# OSSI-1_COMMS_2.net
KiCad netlist of a schematic drawn in Altium Designer
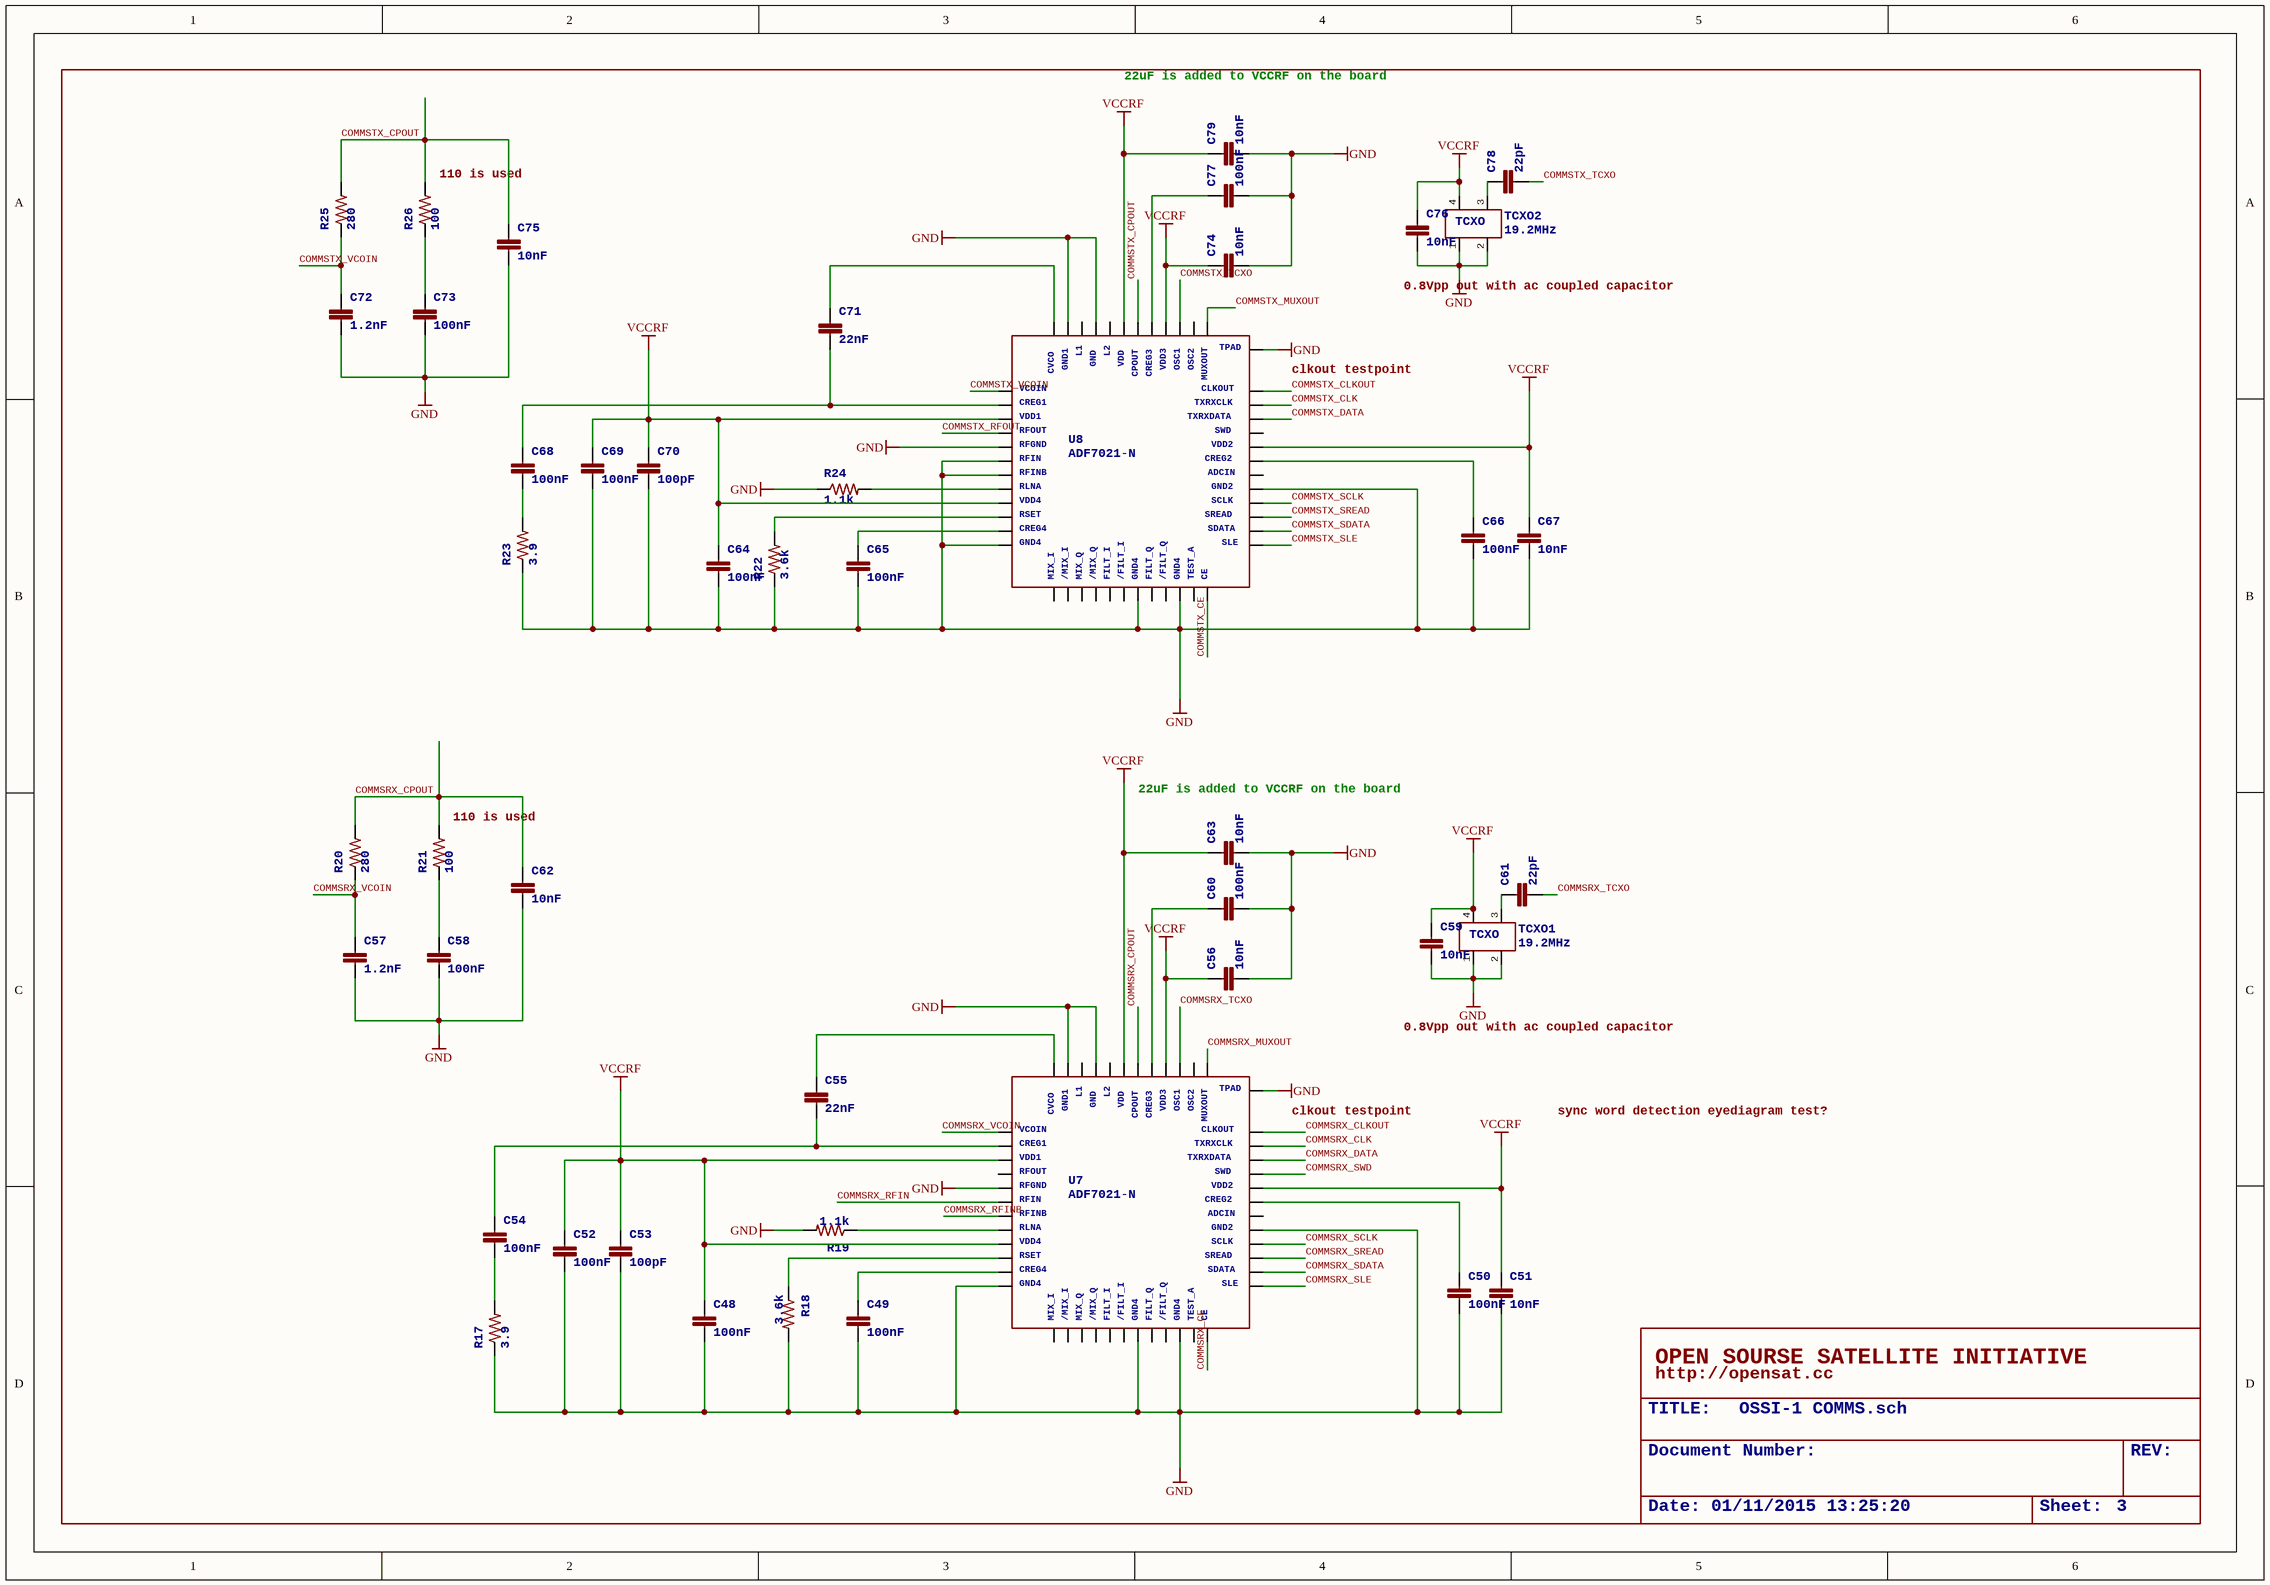
[diagram p0: OSSI-1 COMMS_2.SchDoc]

(export (version "E")
  (design (tool "Eeschema 10.0.6"))
  (components
    (comp (ref "C48")
      (value "100nF")
      (footprint "C0603(1608)")
      (fields (field (name ">NAME") "C48") (field (name ">VALUE") "100nF"))
      (libsource (lib "OSSI") (part "C0603(1608)"))
    )
    (comp (ref "C49")
      (value "100nF")
      (footprint "C0603(1608)")
      (fields (field (name ">NAME") "C49") (field (name ">VALUE") "100nF"))
      (libsource (lib "OSSI") (part "C0603(1608)"))
    )
    (comp (ref "C50")
      (value "100nF")
      (footprint "C0603(1608)")
      (fields (field (name ">NAME") "C50") (field (name ">VALUE") "100nF"))
      (libsource (lib "OSSI") (part "C0603(1608)"))
    )
    (comp (ref "C51")
      (value "10nF")
      (footprint "C0603(1608)")
      (fields (field (name ">NAME") "C51") (field (name ">VALUE") "10nF"))
      (libsource (lib "OSSI") (part "C0603(1608)"))
    )
    (comp (ref "C52")
      (value "100nF")
      (footprint "C0603(1608)")
      (fields (field (name ">NAME") "C52") (field (name ">VALUE") "100nF"))
      (libsource (lib "OSSI") (part "C0603(1608)"))
    )
    (comp (ref "C53")
      (value "100pF")
      (footprint "C0603(1608)")
      (fields (field (name ">NAME") "C53") (field (name ">VALUE") "100pF"))
      (libsource (lib "OSSI") (part "C0603(1608)"))
    )
    (comp (ref "C54")
      (value "100nF")
      (footprint "C0603(1608)")
      (fields (field (name ">NAME") "C54") (field (name ">VALUE") "100nF"))
      (libsource (lib "OSSI") (part "C0603(1608)"))
    )
    (comp (ref "C55")
      (value "22nF")
      (footprint "C0603(1608)")
      (fields (field (name ">NAME") "C55") (field (name ">VALUE") "22nF"))
      (libsource (lib "OSSI") (part "C0603(1608)"))
    )
    (comp (ref "C56")
      (value "10nF")
      (footprint "C0603(1608)")
      (fields (field (name ">NAME") "C56") (field (name ">VALUE") "10nF"))
      (libsource (lib "") (part "C0603(1608)_1"))
    )
    (comp (ref "C57")
      (value "1.2nF")
      (footprint "C0603(1608)")
      (fields (field (name ">NAME") "C57") (field (name ">VALUE") "1.2nF"))
      (libsource (lib "OSSI") (part "C0603(1608)"))
    )
    (comp (ref "C58")
      (value "100nF")
      (footprint "C0603(1608)")
      (fields (field (name ">NAME") "C58") (field (name ">VALUE") "100nF"))
      (libsource (lib "OSSI") (part "C0603(1608)"))
    )
    (comp (ref "C59")
      (value "10nF")
      (footprint "C0603(1608)")
      (fields (field (name ">NAME") "C59") (field (name ">VALUE") "10nF"))
      (libsource (lib "OSSI") (part "C0603(1608)"))
    )
    (comp (ref "C60")
      (value "100nF")
      (footprint "C0603(1608)")
      (fields (field (name ">NAME") "C60") (field (name ">VALUE") "100nF"))
      (libsource (lib "") (part "C0603(1608)_1"))
    )
    (comp (ref "C61")
      (value "22pF")
      (footprint "C0603(1608)")
      (fields (field (name ">NAME") "C61") (field (name ">VALUE") "22pF"))
      (libsource (lib "") (part "C0603(1608)_1"))
    )
    (comp (ref "C62")
      (value "10nF")
      (footprint "C0603(1608)")
      (fields (field (name ">NAME") "C62") (field (name ">VALUE") "10nF"))
      (libsource (lib "OSSI") (part "C0603(1608)"))
    )
    (comp (ref "C63")
      (value "10nF")
      (footprint "C0603(1608)")
      (fields (field (name ">NAME") "C63") (field (name ">VALUE") "10nF"))
      (libsource (lib "") (part "C0603(1608)_1"))
    )
    (comp (ref "C64")
      (value "100nF")
      (footprint "C0603(1608)")
      (fields (field (name ">NAME") "C64") (field (name ">VALUE") "100nF"))
      (libsource (lib "OSSI") (part "C0603(1608)"))
    )
    (comp (ref "C65")
      (value "100nF")
      (footprint "C0603(1608)")
      (fields (field (name ">NAME") "C65") (field (name ">VALUE") "100nF"))
      (libsource (lib "OSSI") (part "C0603(1608)"))
    )
    (comp (ref "C66")
      (value "100nF")
      (footprint "C0603(1608)")
      (fields (field (name ">NAME") "C66") (field (name ">VALUE") "100nF"))
      (libsource (lib "OSSI") (part "C0603(1608)"))
    )
    (comp (ref "C67")
      (value "10nF")
      (footprint "C0603(1608)")
      (fields (field (name ">NAME") "C67") (field (name ">VALUE") "10nF"))
      (libsource (lib "OSSI") (part "C0603(1608)"))
    )
    (comp (ref "C68")
      (value "100nF")
      (footprint "C0603(1608)")
      (fields (field (name ">NAME") "C68") (field (name ">VALUE") "100nF"))
      (libsource (lib "OSSI") (part "C0603(1608)"))
    )
    (comp (ref "C69")
      (value "100nF")
      (footprint "C0603(1608)")
      (fields (field (name ">NAME") "C69") (field (name ">VALUE") "100nF"))
      (libsource (lib "OSSI") (part "C0603(1608)"))
    )
    (comp (ref "C70")
      (value "100pF")
      (footprint "C0603(1608)")
      (fields (field (name ">NAME") "C70") (field (name ">VALUE") "100pF"))
      (libsource (lib "OSSI") (part "C0603(1608)"))
    )
    (comp (ref "C71")
      (value "22nF")
      (footprint "C0603(1608)")
      (fields (field (name ">NAME") "C71") (field (name ">VALUE") "22nF"))
      (libsource (lib "OSSI") (part "C0603(1608)"))
    )
    (comp (ref "C72")
      (value "1.2nF")
      (footprint "C0603(1608)")
      (fields (field (name ">NAME") "C72") (field (name ">VALUE") "1.2nF"))
      (libsource (lib "OSSI") (part "C0603(1608)"))
    )
    (comp (ref "C73")
      (value "100nF")
      (footprint "C0603(1608)")
      (fields (field (name ">NAME") "C73") (field (name ">VALUE") "100nF"))
      (libsource (lib "OSSI") (part "C0603(1608)"))
    )
    (comp (ref "C74")
      (value "10nF")
      (footprint "C0603(1608)")
      (fields (field (name ">NAME") "C74") (field (name ">VALUE") "10nF"))
      (libsource (lib "") (part "C0603(1608)_1"))
    )
    (comp (ref "C75")
      (value "10nF")
      (footprint "C0603(1608)")
      (fields (field (name ">NAME") "C75") (field (name ">VALUE") "10nF"))
      (libsource (lib "OSSI") (part "C0603(1608)"))
    )
    (comp (ref "C76")
      (value "10nF")
      (footprint "C0603(1608)")
      (fields (field (name ">NAME") "C76") (field (name ">VALUE") "10nF"))
      (libsource (lib "OSSI") (part "C0603(1608)"))
    )
    (comp (ref "C77")
      (value "100nF")
      (footprint "C0603(1608)")
      (fields (field (name ">NAME") "C77") (field (name ">VALUE") "100nF"))
      (libsource (lib "") (part "C0603(1608)_1"))
    )
    (comp (ref "C78")
      (value "22pF")
      (footprint "C0603(1608)")
      (fields (field (name ">NAME") "C78") (field (name ">VALUE") "22pF"))
      (libsource (lib "") (part "C0603(1608)_1"))
    )
    (comp (ref "C79")
      (value "10nF")
      (footprint "C0603(1608)")
      (fields (field (name ">NAME") "C79") (field (name ">VALUE") "10nF"))
      (libsource (lib "") (part "C0603(1608)_1"))
    )
    (comp (ref "R17")
      (value "3.9")
      (footprint "R0603(1608)")
      (fields (field (name ">NAME") "R17") (field (name ">VALUE") "3.9"))
      (libsource (lib "OSSI") (part "R0603(1608)"))
    )
    (comp (ref "R18")
      (value "3.6k")
      (footprint "R0603(1608)")
      (fields (field (name ">NAME") "R18") (field (name ">VALUE") "3.6k"))
      (libsource (lib "OSSI") (part "R0603(1608)"))
    )
    (comp (ref "R19")
      (value "1.1k")
      (footprint "R0603(1608)")
      (fields (field (name ">NAME") "R19") (field (name ">VALUE") "1.1k"))
      (libsource (lib "OSSI") (part "R0603(1608)"))
    )
    (comp (ref "R20")
      (value "280")
      (footprint "R0603(1608)")
      (fields (field (name ">NAME") "R20") (field (name ">VALUE") "280"))
      (libsource (lib "OSSI") (part "R0603(1608)"))
    )
    (comp (ref "R21")
      (value "100")
      (footprint "R0603(1608)")
      (fields (field (name ">NAME") "R21") (field (name ">VALUE") "100"))
      (libsource (lib "OSSI") (part "R0603(1608)"))
    )
    (comp (ref "R22")
      (value "3.6k")
      (footprint "R0603(1608)")
      (fields (field (name ">NAME") "R22") (field (name ">VALUE") "3.6k"))
      (libsource (lib "OSSI") (part "R0603(1608)"))
    )
    (comp (ref "R23")
      (value "3.9")
      (footprint "R0603(1608)")
      (fields (field (name ">NAME") "R23") (field (name ">VALUE") "3.9"))
      (libsource (lib "OSSI") (part "R0603(1608)"))
    )
    (comp (ref "R24")
      (value "1.1k")
      (footprint "R0603(1608)")
      (fields (field (name ">NAME") "R24") (field (name ">VALUE") "1.1k"))
      (libsource (lib "OSSI") (part "R0603(1608)"))
    )
    (comp (ref "R25")
      (value "280")
      (footprint "R0603(1608)")
      (fields (field (name ">NAME") "R25") (field (name ">VALUE") "280"))
      (libsource (lib "OSSI") (part "R0603(1608)"))
    )
    (comp (ref "R26")
      (value "100")
      (footprint "R0603(1608)")
      (fields (field (name ">NAME") "R26") (field (name ">VALUE") "100"))
      (libsource (lib "OSSI") (part "R0603(1608)"))
    )
    (comp (ref "TCXO1")
      (value "19.2MHz")
      (footprint "TCXO_M532")
      (fields (field (name "TCXO") "TCXO") (field (name ">NAME") "TCXO1") (field (name ">VALUE") "19.2MHz"))
      (libsource (lib "OSSI") (part "TCXO-M532"))
    )
    (comp (ref "TCXO2")
      (value "19.2MHz")
      (footprint "TCXO_M532")
      (fields (field (name "TCXO") "TCXO") (field (name ">NAME") "TCXO2") (field (name ">VALUE") "19.2MHz"))
      (libsource (lib "OSSI") (part "TCXO-M532"))
    )
    (comp (ref "U7")
      (value "ADF7021-N")
      (footprint "LFCSP48")
      (description "<B>ADF7021-N</B>\n<br />\nRF transceiver from analog device")
      (fields
        (field (name "VCOIN") "VCOIN")
        (field (name "CREG1") "CREG1")
        (field (name "VDD1") "VDD1")
        (field (name "RFOUT") "RFOUT")
        (field (name "RFGND") "RFGND")
        (field (name "RFIN") "RFIN")
        (field (name "RFINB") "RFINB")
        (field (name "RLNA") "RLNA")
        (field (name "VDD4") "VDD4")
        (field (name "RSET") "RSET")
        (field (name "CREG4") "CREG4")
        (field (name "GND4") "GND4")
        (field (name "MIX_I") "MIX_I")
        (field (name "/MIX_I") "/MIX_I")
        (field (name "MIX_Q") "MIX_Q")
        (field (name "/MIX_Q") "/MIX_Q")
        (field (name "FILT_I") "FILT_I")
        (field (name "/FILT_I") "/FILT_I")
        (field (name "GND4_1") "GND4")
        (field (name "TEST_A") "TEST_A")
        (field (name "FILT_Q") "FILT_Q")
        (field (name "/FILT_Q") "/FILT_Q")
        (field (name "GND4_2") "GND4")
        (field (name "CE") "CE")
        (field (name "SLE") "SLE")
        (field (name "SDATA") "SDATA")
        (field (name "SREAD") "SREAD")
        (field (name "SCLK") "SCLK")
        (field (name "GND2") "GND2")
        (field (name "ADCIN") "ADCIN")
        (field (name "CREG2") "CREG2")
        (field (name "VDD2") "VDD2")
        (field (name "SWD") "SWD")
        (field (name "TXRXDATA") "TXRXDATA")
        (field (name "TXRXCLK") "TXRXCLK")
        (field (name "CLKOUT") "CLKOUT")
        (field (name "MUXOUT") "MUXOUT")
        (field (name "OSC2") "OSC2")
        (field (name "OSC1") "OSC1")
        (field (name "VDD3") "VDD3")
        (field (name "CREG3") "CREG3")
        (field (name "CPOUT") "CPOUT")
        (field (name "VDD") "VDD")
        (field (name "L2") "L2")
        (field (name "GND") "GND")
        (field (name "L1") "L1")
        (field (name "GND1") "GND1")
        (field (name "CVCO") "CVCO")
        (field (name ">NAME") "U7")
        (field (name ">VALUE") "ADF7021-N")
        (field (name "TPAD") "TPAD")
      )
      (libsource (lib "OSSI") (part "ADF7021-N"))
    )
    (comp (ref "U8")
      (value "ADF7021-N")
      (footprint "LFCSP48")
      (description "<B>ADF7021-N</B>\n<br />\nRF transceiver from analog device")
      (fields
        (field (name "VCOIN") "VCOIN")
        (field (name "CREG1") "CREG1")
        (field (name "VDD1") "VDD1")
        (field (name "RFOUT") "RFOUT")
        (field (name "RFGND") "RFGND")
        (field (name "RFIN") "RFIN")
        (field (name "RFINB") "RFINB")
        (field (name "RLNA") "RLNA")
        (field (name "VDD4") "VDD4")
        (field (name "RSET") "RSET")
        (field (name "CREG4") "CREG4")
        (field (name "GND4") "GND4")
        (field (name "MIX_I") "MIX_I")
        (field (name "/MIX_I") "/MIX_I")
        (field (name "MIX_Q") "MIX_Q")
        (field (name "/MIX_Q") "/MIX_Q")
        (field (name "FILT_I") "FILT_I")
        (field (name "/FILT_I") "/FILT_I")
        (field (name "GND4_1") "GND4")
        (field (name "TEST_A") "TEST_A")
        (field (name "FILT_Q") "FILT_Q")
        (field (name "/FILT_Q") "/FILT_Q")
        (field (name "GND4_2") "GND4")
        (field (name "CE") "CE")
        (field (name "SLE") "SLE")
        (field (name "SDATA") "SDATA")
        (field (name "SREAD") "SREAD")
        (field (name "SCLK") "SCLK")
        (field (name "GND2") "GND2")
        (field (name "ADCIN") "ADCIN")
        (field (name "CREG2") "CREG2")
        (field (name "VDD2") "VDD2")
        (field (name "SWD") "SWD")
        (field (name "TXRXDATA") "TXRXDATA")
        (field (name "TXRXCLK") "TXRXCLK")
        (field (name "CLKOUT") "CLKOUT")
        (field (name "MUXOUT") "MUXOUT")
        (field (name "OSC2") "OSC2")
        (field (name "OSC1") "OSC1")
        (field (name "VDD3") "VDD3")
        (field (name "CREG3") "CREG3")
        (field (name "CPOUT") "CPOUT")
        (field (name "VDD") "VDD")
        (field (name "L2") "L2")
        (field (name "GND") "GND")
        (field (name "L1") "L1")
        (field (name "GND1") "GND1")
        (field (name "CVCO") "CVCO")
        (field (name ">NAME") "U8")
        (field (name ">VALUE") "ADF7021-N")
        (field (name "TPAD") "TPAD")
      )
      (libsource (lib "OSSI") (part "ADF7021-N"))
    )
  )
  (nets
    (net (code "1") (name "/COMMSRX_CE") (class "Default")
      (node (ref "U7") (pin "24") (pinfunction "P$24_24") (pintype "passive"))
    )
    (net (code "2") (name "/COMMSRX_CLK") (class "Default")
      (node (ref "U7") (pin "35") (pinfunction "P$35_35") (pintype "passive"))
    )
    (net (code "3") (name "/COMMSRX_CLKOUT") (class "Default")
      (node (ref "U7") (pin "36") (pinfunction "P$36_36") (pintype "passive"))
    )
    (net (code "4") (name "/COMMSRX_CPOUT") (class "Default")
      (node (ref "C62") (pin "1") (pinfunction "1_1") (pintype "passive"))
      (node (ref "R20") (pin "2") (pinfunction "2_2") (pintype "passive"))
      (node (ref "R21") (pin "2") (pinfunction "2_2") (pintype "passive"))
      (node (ref "U7") (pin "42") (pinfunction "P$42_42") (pintype "passive"))
    )
    (net (code "5") (name "/COMMSRX_DATA") (class "Default")
      (node (ref "U7") (pin "34") (pinfunction "P$34_34") (pintype "passive"))
    )
    (net (code "6") (name "/COMMSRX_MUXOUT") (class "Default")
      (node (ref "U7") (pin "37") (pinfunction "P$37_37") (pintype "passive"))
    )
    (net (code "7") (name "/COMMSRX_RFIN") (class "Default")
      (node (ref "U7") (pin "6") (pinfunction "P$6_6") (pintype "passive"))
    )
    (net (code "8") (name "/COMMSRX_RFINB") (class "Default")
      (node (ref "U7") (pin "7") (pinfunction "P$7_7") (pintype "passive"))
    )
    (net (code "9") (name "/COMMSRX_SCLK") (class "Default")
      (node (ref "U7") (pin "28") (pinfunction "P$28_28") (pintype "passive"))
    )
    (net (code "10") (name "/COMMSRX_SDATA") (class "Default")
      (node (ref "U7") (pin "26") (pinfunction "P$26_26") (pintype "passive"))
    )
    (net (code "11") (name "/COMMSRX_SLE") (class "Default")
      (node (ref "U7") (pin "25") (pinfunction "P$25_25") (pintype "passive"))
    )
    (net (code "12") (name "/COMMSRX_SREAD") (class "Default")
      (node (ref "U7") (pin "27") (pinfunction "P$27_27") (pintype "passive"))
    )
    (net (code "13") (name "/COMMSRX_SWD") (class "Default")
      (node (ref "U7") (pin "33") (pinfunction "P$33_33") (pintype "passive"))
    )
    (net (code "14") (name "/COMMSRX_TCXO") (class "Default")
      (node (ref "C61") (pin "2") (pinfunction "2_2") (pintype "passive"))
      (node (ref "U7") (pin "39") (pinfunction "P$39_39") (pintype "passive"))
    )
    (net (code "15") (name "/COMMSRX_VCOIN") (class "Default")
      (node (ref "C57") (pin "1") (pinfunction "1_1") (pintype "passive"))
      (node (ref "R20") (pin "1") (pinfunction "1_1") (pintype "passive"))
      (node (ref "U7") (pin "1") (pinfunction "P$1_1") (pintype "passive"))
    )
    (net (code "16") (name "/COMMSTX_CE") (class "Default")
      (node (ref "U8") (pin "24") (pinfunction "P$24_24") (pintype "passive"))
    )
    (net (code "17") (name "/COMMSTX_CLK") (class "Default")
      (node (ref "U8") (pin "35") (pinfunction "P$35_35") (pintype "passive"))
    )
    (net (code "18") (name "/COMMSTX_CLKOUT") (class "Default")
      (node (ref "U8") (pin "36") (pinfunction "P$36_36") (pintype "passive"))
    )
    (net (code "19") (name "/COMMSTX_CPOUT") (class "Default")
      (node (ref "C75") (pin "1") (pinfunction "1_1") (pintype "passive"))
      (node (ref "R25") (pin "2") (pinfunction "2_2") (pintype "passive"))
      (node (ref "R26") (pin "2") (pinfunction "2_2") (pintype "passive"))
      (node (ref "U8") (pin "42") (pinfunction "P$42_42") (pintype "passive"))
    )
    (net (code "20") (name "/COMMSTX_DATA") (class "Default")
      (node (ref "U8") (pin "34") (pinfunction "P$34_34") (pintype "passive"))
    )
    (net (code "21") (name "/COMMSTX_MUXOUT") (class "Default")
      (node (ref "U8") (pin "37") (pinfunction "P$37_37") (pintype "passive"))
    )
    (net (code "22") (name "/COMMSTX_RFOUT") (class "Default")
      (node (ref "U8") (pin "4") (pinfunction "P$4_4") (pintype "passive"))
    )
    (net (code "23") (name "/COMMSTX_SCLK") (class "Default")
      (node (ref "U8") (pin "28") (pinfunction "P$28_28") (pintype "passive"))
    )
    (net (code "24") (name "/COMMSTX_SDATA") (class "Default")
      (node (ref "U8") (pin "26") (pinfunction "P$26_26") (pintype "passive"))
    )
    (net (code "25") (name "/COMMSTX_SLE") (class "Default")
      (node (ref "U8") (pin "25") (pinfunction "P$25_25") (pintype "passive"))
    )
    (net (code "26") (name "/COMMSTX_SREAD") (class "Default")
      (node (ref "U8") (pin "27") (pinfunction "P$27_27") (pintype "passive"))
    )
    (net (code "27") (name "/COMMSTX_TCXO") (class "Default")
      (node (ref "C78") (pin "2") (pinfunction "2_2") (pintype "passive"))
      (node (ref "U8") (pin "39") (pinfunction "P$39_39") (pintype "passive"))
    )
    (net (code "28") (name "/COMMSTX_VCOIN") (class "Default")
      (node (ref "C72") (pin "1") (pinfunction "1_1") (pintype "passive"))
      (node (ref "R25") (pin "1") (pinfunction "1_1") (pintype "passive"))
      (node (ref "U8") (pin "1") (pinfunction "P$1_1") (pintype "passive"))
    )
    (net (code "29") (name "GND") (class "Default")
      (node (ref "C48") (pin "2") (pinfunction "2_2") (pintype "passive"))
      (node (ref "C49") (pin "2") (pinfunction "2_2") (pintype "passive"))
      (node (ref "C50") (pin "2") (pinfunction "2_2") (pintype "passive"))
      (node (ref "C51") (pin "2") (pinfunction "2_2") (pintype "passive"))
      (node (ref "C52") (pin "2") (pinfunction "2_2") (pintype "passive"))
      (node (ref "C53") (pin "2") (pinfunction "2_2") (pintype "passive"))
      (node (ref "C56") (pin "2") (pinfunction "2_2") (pintype "passive"))
      (node (ref "C57") (pin "2") (pinfunction "2_2") (pintype "passive"))
      (node (ref "C58") (pin "2") (pinfunction "2_2") (pintype "passive"))
      (node (ref "C59") (pin "2") (pinfunction "2_2") (pintype "passive"))
      (node (ref "C60") (pin "2") (pinfunction "2_2") (pintype "passive"))
      (node (ref "C62") (pin "2") (pinfunction "2_2") (pintype "passive"))
      (node (ref "C63") (pin "2") (pinfunction "2_2") (pintype "passive"))
      (node (ref "C64") (pin "2") (pinfunction "2_2") (pintype "passive"))
      (node (ref "C65") (pin "2") (pinfunction "2_2") (pintype "passive"))
      (node (ref "C66") (pin "2") (pinfunction "2_2") (pintype "passive"))
      (node (ref "C67") (pin "2") (pinfunction "2_2") (pintype "passive"))
      (node (ref "C69") (pin "2") (pinfunction "2_2") (pintype "passive"))
      (node (ref "C70") (pin "2") (pinfunction "2_2") (pintype "passive"))
      (node (ref "C72") (pin "2") (pinfunction "2_2") (pintype "passive"))
      (node (ref "C73") (pin "2") (pinfunction "2_2") (pintype "passive"))
      (node (ref "C74") (pin "2") (pinfunction "2_2") (pintype "passive"))
      (node (ref "C75") (pin "2") (pinfunction "2_2") (pintype "passive"))
      (node (ref "C76") (pin "2") (pinfunction "2_2") (pintype "passive"))
      (node (ref "C77") (pin "2") (pinfunction "2_2") (pintype "passive"))
      (node (ref "C79") (pin "2") (pinfunction "2_2") (pintype "passive"))
      (node (ref "R17") (pin "1") (pinfunction "1_1") (pintype "passive"))
      (node (ref "R18") (pin "2") (pinfunction "2_2") (pintype "passive"))
      (node (ref "R19") (pin "2") (pinfunction "2_2") (pintype "passive"))
      (node (ref "R22") (pin "1") (pinfunction "1_1") (pintype "passive"))
      (node (ref "R23") (pin "1") (pinfunction "1_1") (pintype "passive"))
      (node (ref "R24") (pin "1") (pinfunction "1_1") (pintype "passive"))
      (node (ref "TCXO1") (pin "1") (pinfunction "P$1_1") (pintype "passive"))
      (node (ref "TCXO1") (pin "2") (pinfunction "P$2_2") (pintype "passive"))
      (node (ref "TCXO2") (pin "1") (pinfunction "P$1_1") (pintype "passive"))
      (node (ref "TCXO2") (pin "2") (pinfunction "P$2_2") (pintype "passive"))
      (node (ref "U7") (pin "12") (pinfunction "P$12_12") (pintype "passive"))
      (node (ref "U7") (pin "19") (pinfunction "P$19_19") (pintype "passive"))
      (node (ref "U7") (pin "22") (pinfunction "P$22_22") (pintype "passive"))
      (node (ref "U7") (pin "29") (pinfunction "P$29_29") (pintype "passive"))
      (node (ref "U7") (pin "45") (pinfunction "P$45_45") (pintype "passive"))
      (node (ref "U7") (pin "47") (pinfunction "P$47_47") (pintype "passive"))
      (node (ref "U7") (pin "5") (pinfunction "P$5_5") (pintype "passive"))
      (node (ref "U7") (pin "EXP") (pinfunction "P$49_EXP") (pintype "passive"))
      (node (ref "U8") (pin "12") (pinfunction "P$12_12") (pintype "passive"))
      (node (ref "U8") (pin "19") (pinfunction "P$19_19") (pintype "passive"))
      (node (ref "U8") (pin "22") (pinfunction "P$22_22") (pintype "passive"))
      (node (ref "U8") (pin "29") (pinfunction "P$29_29") (pintype "passive"))
      (node (ref "U8") (pin "45") (pinfunction "P$45_45") (pintype "passive"))
      (node (ref "U8") (pin "47") (pinfunction "P$47_47") (pintype "passive"))
      (node (ref "U8") (pin "5") (pinfunction "P$5_5") (pintype "passive"))
      (node (ref "U8") (pin "6") (pinfunction "P$6_6") (pintype "passive"))
      (node (ref "U8") (pin "7") (pinfunction "P$7_7") (pintype "passive"))
      (node (ref "U8") (pin "EXP") (pinfunction "P$49_EXP") (pintype "passive"))
    )
    (net (code "30") (name "Net-(C54-Pad2)") (class "Default")
      (node (ref "C54") (pin "2") (pinfunction "2_2") (pintype "passive"))
      (node (ref "R17") (pin "2") (pinfunction "2_2") (pintype "passive"))
    )
    (net (code "31") (name "Net-(C58-Pad1)") (class "Default")
      (node (ref "C58") (pin "1") (pinfunction "1_1") (pintype "passive"))
      (node (ref "R21") (pin "1") (pinfunction "1_1") (pintype "passive"))
    )
    (net (code "32") (name "Net-(C68-Pad2)") (class "Default")
      (node (ref "C68") (pin "2") (pinfunction "2_2") (pintype "passive"))
      (node (ref "R23") (pin "2") (pinfunction "2_2") (pintype "passive"))
    )
    (net (code "33") (name "Net-(C73-Pad1)") (class "Default")
      (node (ref "C73") (pin "1") (pinfunction "1_1") (pintype "passive"))
      (node (ref "R26") (pin "1") (pinfunction "1_1") (pintype "passive"))
    )
    (net (code "34") (name "Net-(TCXO1-P$3)") (class "Default")
      (node (ref "C61") (pin "1") (pinfunction "1_1") (pintype "passive"))
      (node (ref "TCXO1") (pin "3") (pinfunction "P$3_3") (pintype "passive"))
    )
    (net (code "35") (name "Net-(TCXO2-P$3)") (class "Default")
      (node (ref "C78") (pin "1") (pinfunction "1_1") (pintype "passive"))
      (node (ref "TCXO2") (pin "3") (pinfunction "P$3_3") (pintype "passive"))
    )
    (net (code "36") (name "Net-(U7-P$2)") (class "Default")
      (node (ref "C54") (pin "1") (pinfunction "1_1") (pintype "passive"))
      (node (ref "C55") (pin "2") (pinfunction "2_2") (pintype "passive"))
      (node (ref "U7") (pin "2") (pinfunction "P$2_2") (pintype "passive"))
    )
    (net (code "37") (name "Net-(U7-P$8)") (class "Default")
      (node (ref "R19") (pin "1") (pinfunction "1_1") (pintype "passive"))
      (node (ref "U7") (pin "8") (pinfunction "P$8_8") (pintype "passive"))
    )
    (net (code "38") (name "Net-(U7-P$10)") (class "Default")
      (node (ref "R18") (pin "1") (pinfunction "1_1") (pintype "passive"))
      (node (ref "U7") (pin "10") (pinfunction "P$10_10") (pintype "passive"))
    )
    (net (code "39") (name "Net-(U7-P$11)") (class "Default")
      (node (ref "C49") (pin "1") (pinfunction "1_1") (pintype "passive"))
      (node (ref "U7") (pin "11") (pinfunction "P$11_11") (pintype "passive"))
    )
    (net (code "40") (name "Net-(U7-P$31)") (class "Default")
      (node (ref "C50") (pin "1") (pinfunction "1_1") (pintype "passive"))
      (node (ref "U7") (pin "31") (pinfunction "P$31_31") (pintype "passive"))
    )
    (net (code "41") (name "Net-(U7-P$41)") (class "Default")
      (node (ref "C60") (pin "1") (pinfunction "1_1") (pintype "passive"))
      (node (ref "U7") (pin "41") (pinfunction "P$41_41") (pintype "passive"))
    )
    (net (code "42") (name "Net-(U7-P$48)") (class "Default")
      (node (ref "C55") (pin "1") (pinfunction "1_1") (pintype "passive"))
      (node (ref "U7") (pin "48") (pinfunction "P$48_48") (pintype "passive"))
    )
    (net (code "43") (name "Net-(U8-P$2)") (class "Default")
      (node (ref "C68") (pin "1") (pinfunction "1_1") (pintype "passive"))
      (node (ref "C71") (pin "2") (pinfunction "2_2") (pintype "passive"))
      (node (ref "U8") (pin "2") (pinfunction "P$2_2") (pintype "passive"))
    )
    (net (code "44") (name "Net-(U8-P$8)") (class "Default")
      (node (ref "R24") (pin "2") (pinfunction "2_2") (pintype "passive"))
      (node (ref "U8") (pin "8") (pinfunction "P$8_8") (pintype "passive"))
    )
    (net (code "45") (name "Net-(U8-P$10)") (class "Default")
      (node (ref "R22") (pin "2") (pinfunction "2_2") (pintype "passive"))
      (node (ref "U8") (pin "10") (pinfunction "P$10_10") (pintype "passive"))
    )
    (net (code "46") (name "Net-(U8-P$11)") (class "Default")
      (node (ref "C65") (pin "1") (pinfunction "1_1") (pintype "passive"))
      (node (ref "U8") (pin "11") (pinfunction "P$11_11") (pintype "passive"))
    )
    (net (code "47") (name "Net-(U8-P$31)") (class "Default")
      (node (ref "C66") (pin "1") (pinfunction "1_1") (pintype "passive"))
      (node (ref "U8") (pin "31") (pinfunction "P$31_31") (pintype "passive"))
    )
    (net (code "48") (name "Net-(U8-P$41)") (class "Default")
      (node (ref "C77") (pin "1") (pinfunction "1_1") (pintype "passive"))
      (node (ref "U8") (pin "41") (pinfunction "P$41_41") (pintype "passive"))
    )
    (net (code "49") (name "Net-(U8-P$48)") (class "Default")
      (node (ref "C71") (pin "1") (pinfunction "1_1") (pintype "passive"))
      (node (ref "U8") (pin "48") (pinfunction "P$48_48") (pintype "passive"))
    )
    (net (code "50") (name "VCCRF") (class "Default")
      (node (ref "C48") (pin "1") (pinfunction "1_1") (pintype "passive"))
      (node (ref "C51") (pin "1") (pinfunction "1_1") (pintype "passive"))
      (node (ref "C52") (pin "1") (pinfunction "1_1") (pintype "passive"))
      (node (ref "C53") (pin "1") (pinfunction "1_1") (pintype "passive"))
      (node (ref "C56") (pin "1") (pinfunction "1_1") (pintype "passive"))
      (node (ref "C59") (pin "1") (pinfunction "1_1") (pintype "passive"))
      (node (ref "C63") (pin "1") (pinfunction "1_1") (pintype "passive"))
      (node (ref "C64") (pin "1") (pinfunction "1_1") (pintype "passive"))
      (node (ref "C67") (pin "1") (pinfunction "1_1") (pintype "passive"))
      (node (ref "C69") (pin "1") (pinfunction "1_1") (pintype "passive"))
      (node (ref "C70") (pin "1") (pinfunction "1_1") (pintype "passive"))
      (node (ref "C74") (pin "1") (pinfunction "1_1") (pintype "passive"))
      (node (ref "C76") (pin "1") (pinfunction "1_1") (pintype "passive"))
      (node (ref "C79") (pin "1") (pinfunction "1_1") (pintype "passive"))
      (node (ref "TCXO1") (pin "4") (pinfunction "P$4_4") (pintype "passive"))
      (node (ref "TCXO2") (pin "4") (pinfunction "P$4_4") (pintype "passive"))
      (node (ref "U7") (pin "3") (pinfunction "P$3_3") (pintype "passive"))
      (node (ref "U7") (pin "32") (pinfunction "P$32_32") (pintype "passive"))
      (node (ref "U7") (pin "40") (pinfunction "P$40_40") (pintype "passive"))
      (node (ref "U7") (pin "43") (pinfunction "P$43_43") (pintype "passive"))
      (node (ref "U7") (pin "9") (pinfunction "P$9_9") (pintype "passive"))
      (node (ref "U8") (pin "3") (pinfunction "P$3_3") (pintype "passive"))
      (node (ref "U8") (pin "32") (pinfunction "P$32_32") (pintype "passive"))
      (node (ref "U8") (pin "40") (pinfunction "P$40_40") (pintype "passive"))
      (node (ref "U8") (pin "43") (pinfunction "P$43_43") (pintype "passive"))
      (node (ref "U8") (pin "9") (pinfunction "P$9_9") (pintype "passive"))
    )
    (net (code "51") (name "unconnected-(U7-P$4-Pad4)") (class "Default")
      (node (ref "U7") (pin "4") (pinfunction "P$4_4") (pintype "passive"))
    )
    (net (code "52") (name "unconnected-(U7-P$13-Pad13)") (class "Default")
      (node (ref "U7") (pin "13") (pinfunction "P$13_13") (pintype "passive"))
    )
    (net (code "53") (name "unconnected-(U7-P$14-Pad14)") (class "Default")
      (node (ref "U7") (pin "14") (pinfunction "P$14_14") (pintype "passive"))
    )
    (net (code "54") (name "unconnected-(U7-P$15-Pad15)") (class "Default")
      (node (ref "U7") (pin "15") (pinfunction "P$15_15") (pintype "passive"))
    )
    (net (code "55") (name "unconnected-(U7-P$16-Pad16)") (class "Default")
      (node (ref "U7") (pin "16") (pinfunction "P$16_16") (pintype "passive"))
    )
    (net (code "56") (name "unconnected-(U7-P$17-Pad17)") (class "Default")
      (node (ref "U7") (pin "17") (pinfunction "P$17_17") (pintype "passive"))
    )
    (net (code "57") (name "unconnected-(U7-P$18-Pad18)") (class "Default")
      (node (ref "U7") (pin "18") (pinfunction "P$18_18") (pintype "passive"))
    )
    (net (code "58") (name "unconnected-(U7-P$20-Pad20)") (class "Default")
      (node (ref "U7") (pin "20") (pinfunction "P$20_20") (pintype "passive"))
    )
    (net (code "59") (name "unconnected-(U7-P$21-Pad21)") (class "Default")
      (node (ref "U7") (pin "21") (pinfunction "P$21_21") (pintype "passive"))
    )
    (net (code "60") (name "unconnected-(U7-P$23-Pad23)") (class "Default")
      (node (ref "U7") (pin "23") (pinfunction "P$23_23") (pintype "passive"))
    )
    (net (code "61") (name "unconnected-(U7-P$30-Pad30)") (class "Default")
      (node (ref "U7") (pin "30") (pinfunction "P$30_30") (pintype "passive"))
    )
    (net (code "62") (name "unconnected-(U7-P$38-Pad38)") (class "Default")
      (node (ref "U7") (pin "38") (pinfunction "P$38_38") (pintype "passive"))
    )
    (net (code "63") (name "unconnected-(U7-P$44-Pad44)") (class "Default")
      (node (ref "U7") (pin "44") (pinfunction "P$44_44") (pintype "passive"))
    )
    (net (code "64") (name "unconnected-(U7-P$46-Pad46)") (class "Default")
      (node (ref "U7") (pin "46") (pinfunction "P$46_46") (pintype "passive"))
    )
    (net (code "65") (name "unconnected-(U8-P$13-Pad13)") (class "Default")
      (node (ref "U8") (pin "13") (pinfunction "P$13_13") (pintype "passive"))
    )
    (net (code "66") (name "unconnected-(U8-P$14-Pad14)") (class "Default")
      (node (ref "U8") (pin "14") (pinfunction "P$14_14") (pintype "passive"))
    )
    (net (code "67") (name "unconnected-(U8-P$15-Pad15)") (class "Default")
      (node (ref "U8") (pin "15") (pinfunction "P$15_15") (pintype "passive"))
    )
    (net (code "68") (name "unconnected-(U8-P$16-Pad16)") (class "Default")
      (node (ref "U8") (pin "16") (pinfunction "P$16_16") (pintype "passive"))
    )
    (net (code "69") (name "unconnected-(U8-P$17-Pad17)") (class "Default")
      (node (ref "U8") (pin "17") (pinfunction "P$17_17") (pintype "passive"))
    )
    (net (code "70") (name "unconnected-(U8-P$18-Pad18)") (class "Default")
      (node (ref "U8") (pin "18") (pinfunction "P$18_18") (pintype "passive"))
    )
    (net (code "71") (name "unconnected-(U8-P$20-Pad20)") (class "Default")
      (node (ref "U8") (pin "20") (pinfunction "P$20_20") (pintype "passive"))
    )
    (net (code "72") (name "unconnected-(U8-P$21-Pad21)") (class "Default")
      (node (ref "U8") (pin "21") (pinfunction "P$21_21") (pintype "passive"))
    )
    (net (code "73") (name "unconnected-(U8-P$23-Pad23)") (class "Default")
      (node (ref "U8") (pin "23") (pinfunction "P$23_23") (pintype "passive"))
    )
    (net (code "74") (name "unconnected-(U8-P$30-Pad30)") (class "Default")
      (node (ref "U8") (pin "30") (pinfunction "P$30_30") (pintype "passive"))
    )
    (net (code "75") (name "unconnected-(U8-P$33-Pad33)") (class "Default")
      (node (ref "U8") (pin "33") (pinfunction "P$33_33") (pintype "passive"))
    )
    (net (code "76") (name "unconnected-(U8-P$38-Pad38)") (class "Default")
      (node (ref "U8") (pin "38") (pinfunction "P$38_38") (pintype "passive"))
    )
    (net (code "77") (name "unconnected-(U8-P$44-Pad44)") (class "Default")
      (node (ref "U8") (pin "44") (pinfunction "P$44_44") (pintype "passive"))
    )
    (net (code "78") (name "unconnected-(U8-P$46-Pad46)") (class "Default")
      (node (ref "U8") (pin "46") (pinfunction "P$46_46") (pintype "passive"))
    )
  )
)
